# 207.net
KiCad netlist of a schematic drawn in EAGLE
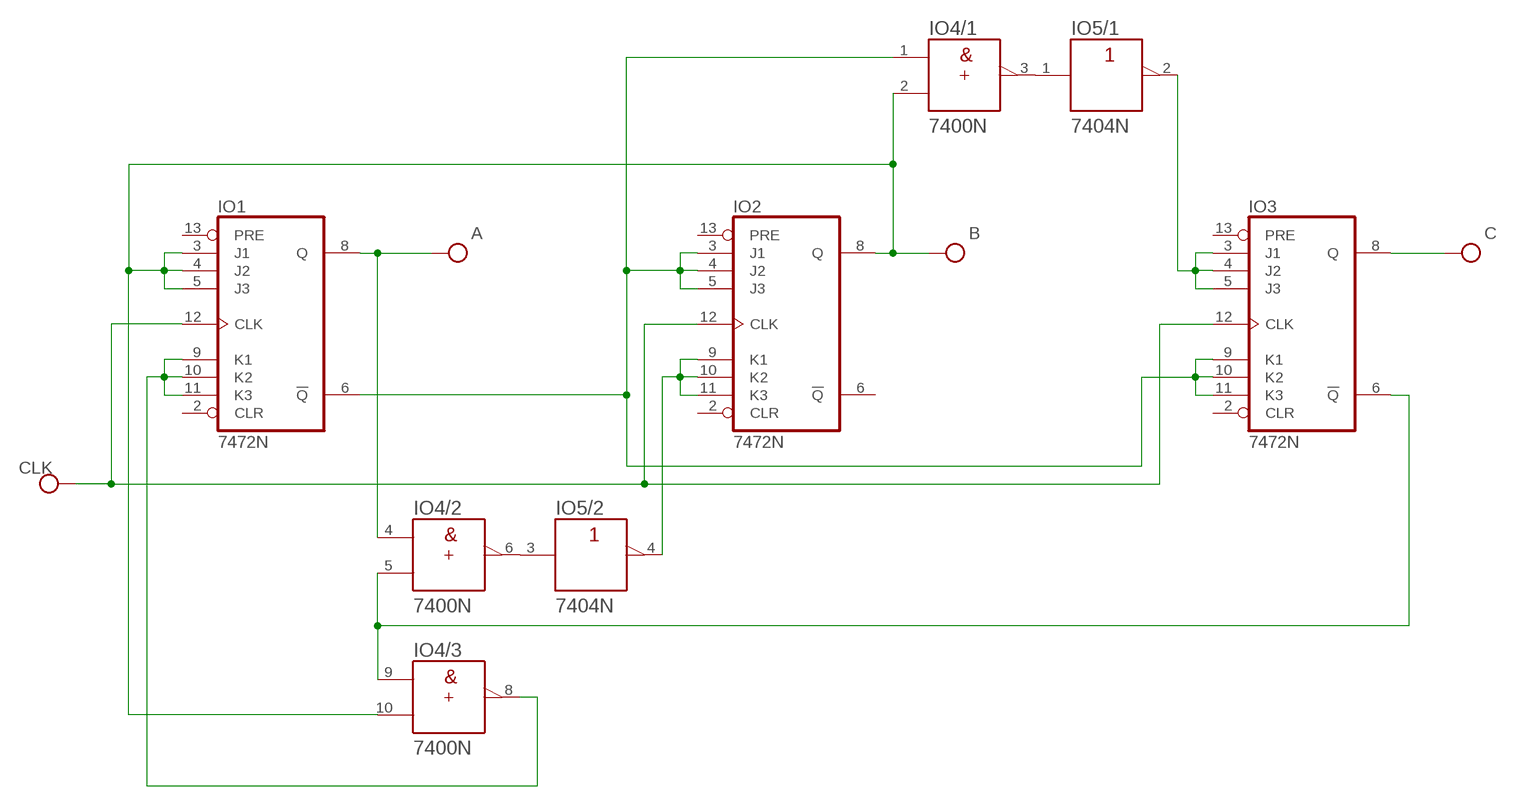
[diagram p0: schematic, sheet 1]

(export (version "E")
  (design (tool "Eeschema 10.0.6"))
  (components
    (comp (ref "IO1")
      (value "7472N")
      (footprint "eagle-import:DIL14")
      (libsource (lib "eagle-import") (part "7472N"))
    )
    (comp (ref "IO2")
      (value "7472N")
      (footprint "eagle-import:DIL14")
      (libsource (lib "eagle-import") (part "7472N"))
    )
    (comp (ref "IO3")
      (value "7472N")
      (footprint "eagle-import:DIL14")
      (libsource (lib "eagle-import") (part "7472N"))
    )
    (comp (ref "IO4")
      (value "7400N")
      (footprint "eagle-import:DIL14")
      (libsource (lib "eagle-import") (part "7400N"))
    )
    (comp (ref "IO5")
      (value "7404N")
      (footprint "eagle-import:DIL14")
      (libsource (lib "eagle-import") (part "7404N"))
    )
  )
  (nets
    (net (code "1") (name "A") (class "Default")
      (node (ref "IO1") (pin "12") (pinfunction "CLK_12") (pintype "input"))
      (node (ref "IO1") (pin "3") (pinfunction "J1_3") (pintype "input"))
      (node (ref "IO1") (pin "4") (pinfunction "J2_4") (pintype "input"))
      (node (ref "IO1") (pin "5") (pinfunction "J3_5") (pintype "input"))
      (node (ref "IO1") (pin "8") (pinfunction "Q_8") (pintype "output"))
      (node (ref "IO2") (pin "12") (pinfunction "CLK_12") (pintype "input"))
      (node (ref "IO2") (pin "8") (pinfunction "Q_8") (pintype "output"))
      (node (ref "IO3") (pin "12") (pinfunction "CLK_12") (pintype "input"))
      (node (ref "IO3") (pin "8") (pinfunction "Q_8") (pintype "output"))
      (node (ref "IO4") (pin "10") (pinfunction "B_10") (pintype "input"))
      (node (ref "IO4") (pin "2") (pinfunction "B_2") (pintype "input"))
      (node (ref "IO4") (pin "4") (pinfunction "A_4") (pintype "input"))
    )
    (net (code "2") (name "Net-(IO1A-K1)") (class "Default")
      (node (ref "IO1") (pin "10") (pinfunction "K2_10") (pintype "input"))
      (node (ref "IO1") (pin "11") (pinfunction "K3_11") (pintype "input"))
      (node (ref "IO1") (pin "9") (pinfunction "K1_9") (pintype "input"))
      (node (ref "IO4") (pin "8") (pinfunction "Y_8") (pintype "output"))
    )
    (net (code "3") (name "Net-(IO1A-~{Q})") (class "Default")
      (node (ref "IO1") (pin "6") (pinfunction "~{Q}_6") (pintype "output"))
      (node (ref "IO2") (pin "3") (pinfunction "J1_3") (pintype "input"))
      (node (ref "IO2") (pin "4") (pinfunction "J2_4") (pintype "input"))
      (node (ref "IO2") (pin "5") (pinfunction "J3_5") (pintype "input"))
      (node (ref "IO3") (pin "10") (pinfunction "K2_10") (pintype "input"))
      (node (ref "IO3") (pin "11") (pinfunction "K3_11") (pintype "input"))
      (node (ref "IO3") (pin "9") (pinfunction "K1_9") (pintype "input"))
      (node (ref "IO4") (pin "1") (pinfunction "A_1") (pintype "input"))
    )
    (net (code "4") (name "Net-(IO2A-K1)") (class "Default")
      (node (ref "IO2") (pin "10") (pinfunction "K2_10") (pintype "input"))
      (node (ref "IO2") (pin "11") (pinfunction "K3_11") (pintype "input"))
      (node (ref "IO2") (pin "9") (pinfunction "K1_9") (pintype "input"))
      (node (ref "IO5") (pin "4") (pinfunction "Y_4") (pintype "output"))
    )
    (net (code "5") (name "Net-(IO3A-J1)") (class "Default")
      (node (ref "IO3") (pin "3") (pinfunction "J1_3") (pintype "input"))
      (node (ref "IO3") (pin "4") (pinfunction "J2_4") (pintype "input"))
      (node (ref "IO3") (pin "5") (pinfunction "J3_5") (pintype "input"))
      (node (ref "IO5") (pin "2") (pinfunction "Y_2") (pintype "output"))
    )
    (net (code "6") (name "Net-(IO3A-~{Q})") (class "Default")
      (node (ref "IO3") (pin "6") (pinfunction "~{Q}_6") (pintype "output"))
      (node (ref "IO4") (pin "5") (pinfunction "B_5") (pintype "input"))
      (node (ref "IO4") (pin "9") (pinfunction "A_9") (pintype "input"))
    )
    (net (code "7") (name "Net-(IO4C-Y)") (class "Default")
      (node (ref "IO4") (pin "3") (pinfunction "Y_3") (pintype "output"))
      (node (ref "IO5") (pin "1") (pinfunction "A_1") (pintype "input"))
    )
    (net (code "8") (name "Net-(IO4D-Y)") (class "Default")
      (node (ref "IO4") (pin "6") (pinfunction "Y_6") (pintype "output"))
      (node (ref "IO5") (pin "3") (pinfunction "A_3") (pintype "input"))
    )
    (net (code "9") (name "unconnected-(IO1A-CLR-Pad2)") (class "Default")
      (node (ref "IO1") (pin "2") (pinfunction "CLR_2") (pintype "input"))
    )
    (net (code "10") (name "unconnected-(IO1A-PRE-Pad13)") (class "Default")
      (node (ref "IO1") (pin "13") (pinfunction "PRE_13") (pintype "input"))
    )
    (net (code "11") (name "unconnected-(IO2A-CLR-Pad2)") (class "Default")
      (node (ref "IO2") (pin "2") (pinfunction "CLR_2") (pintype "input"))
    )
    (net (code "12") (name "unconnected-(IO2A-PRE-Pad13)") (class "Default")
      (node (ref "IO2") (pin "13") (pinfunction "PRE_13") (pintype "input"))
    )
    (net (code "13") (name "unconnected-(IO2A-~{Q}-Pad6)") (class "Default")
      (node (ref "IO2") (pin "6") (pinfunction "~{Q}_6") (pintype "output"))
    )
    (net (code "14") (name "unconnected-(IO3A-CLR-Pad2)") (class "Default")
      (node (ref "IO3") (pin "2") (pinfunction "CLR_2") (pintype "input"))
    )
    (net (code "15") (name "unconnected-(IO3A-PRE-Pad13)") (class "Default")
      (node (ref "IO3") (pin "13") (pinfunction "PRE_13") (pintype "input"))
    )
  )
)
